# untitled.net
KiCad netlist of a schematic drawn in EAGLE
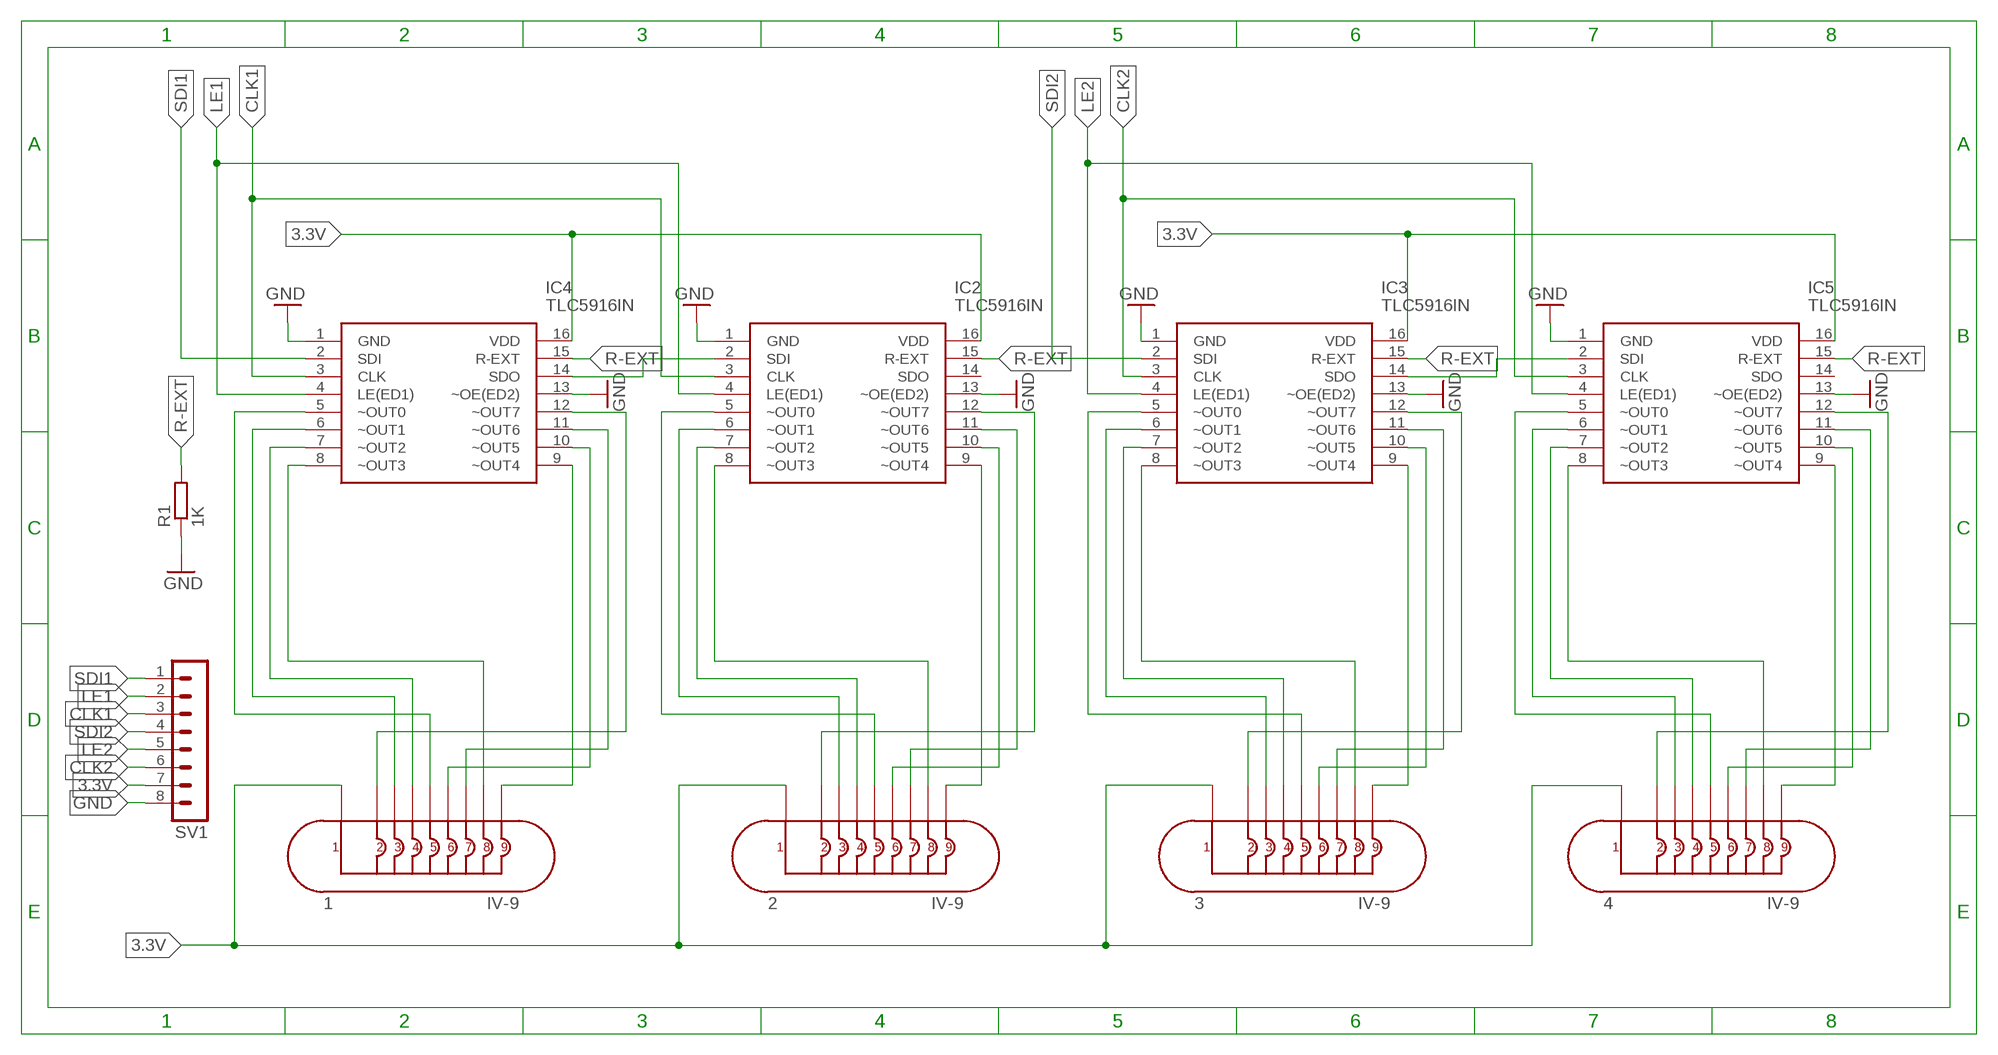
[diagram p0: schematic, sheet 1]
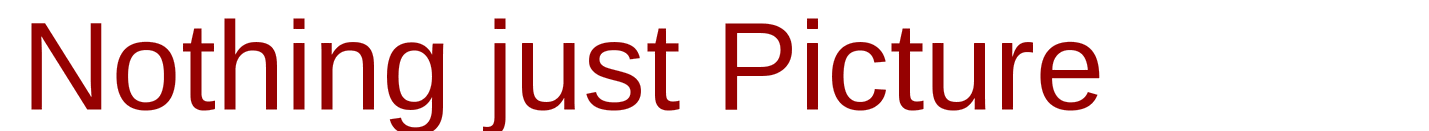
[diagram p1: schematic, sheet 2]

(export (version "E")
  (design (tool "Eeschema 10.0.6"))
  (components
    (comp (ref "1")
      (value "IV-9")
      (footprint "eagle-import:IV-9")
      (libsource (lib "eagle-import") (part "IV-9"))
    )
    (comp (ref "2")
      (value "IV-9")
      (footprint "eagle-import:IV-9")
      (libsource (lib "eagle-import") (part "IV-9"))
    )
    (comp (ref "3")
      (value "IV-9")
      (footprint "eagle-import:IV-9")
      (libsource (lib "eagle-import") (part "IV-9"))
    )
    (comp (ref "4")
      (value "IV-9")
      (footprint "eagle-import:IV-9")
      (libsource (lib "eagle-import") (part "IV-9"))
    )
    (comp (ref "IC2")
      (value "TLC5916IN")
      (footprint "eagle-import:DIP254P762X508-16")
      (fields (field (name "MOUSER_PART_NUMBER") "595-TLC5916IN"))
      (libsource (lib "eagle-import") (part "TLC5916IN"))
    )
    (comp (ref "IC3")
      (value "TLC5916IN")
      (footprint "eagle-import:DIP254P762X508-16")
      (fields (field (name "MOUSER_PART_NUMBER") "595-TLC5916IN"))
      (libsource (lib "eagle-import") (part "TLC5916IN"))
    )
    (comp (ref "IC4")
      (value "TLC5916IN")
      (footprint "eagle-import:DIP254P762X508-16")
      (fields (field (name "MOUSER_PART_NUMBER") "595-TLC5916IN"))
      (libsource (lib "eagle-import") (part "TLC5916IN"))
    )
    (comp (ref "IC5")
      (value "TLC5916IN")
      (footprint "eagle-import:DIP254P762X508-16")
      (fields (field (name "MOUSER_PART_NUMBER") "595-TLC5916IN"))
      (libsource (lib "eagle-import") (part "TLC5916IN"))
    )
    (comp (ref "R1")
      (value "1K")
      (footprint "eagle-import:R1206")
      (libsource (lib "eagle-import") (part "R-EU_R1206"))
    )
    (comp (ref "SV1")
      (value "MA08-1")
      (footprint "eagle-import:MA08-1")
      (libsource (lib "eagle-import") (part "MA08-1"))
    )
  )
  (nets
    (net (code "1") (name "3.3V") (class "Default")
      (node (ref "1") (pin "1") (pinfunction "1_1") (pintype "bidirectional"))
      (node (ref "2") (pin "1") (pinfunction "1_1") (pintype "bidirectional"))
      (node (ref "3") (pin "1") (pinfunction "1_1") (pintype "bidirectional"))
      (node (ref "4") (pin "1") (pinfunction "1_1") (pintype "bidirectional"))
      (node (ref "IC2") (pin "16") (pinfunction "VDD_16") (pintype "bidirectional"))
      (node (ref "IC3") (pin "16") (pinfunction "VDD_16") (pintype "bidirectional"))
      (node (ref "IC4") (pin "16") (pinfunction "VDD_16") (pintype "bidirectional"))
      (node (ref "IC5") (pin "16") (pinfunction "VDD_16") (pintype "bidirectional"))
      (node (ref "SV1") (pin "7") (pinfunction "7_7") (pintype "passive"))
    )
    (net (code "2") (name "CLK1") (class "Default")
      (node (ref "IC2") (pin "3") (pinfunction "CLK_3") (pintype "bidirectional"))
      (node (ref "IC4") (pin "3") (pinfunction "CLK_3") (pintype "bidirectional"))
      (node (ref "SV1") (pin "3") (pinfunction "3_3") (pintype "passive"))
    )
    (net (code "3") (name "CLK2") (class "Default")
      (node (ref "IC3") (pin "3") (pinfunction "CLK_3") (pintype "bidirectional"))
      (node (ref "IC5") (pin "3") (pinfunction "CLK_3") (pintype "bidirectional"))
      (node (ref "SV1") (pin "6") (pinfunction "6_6") (pintype "passive"))
    )
    (net (code "4") (name "GND") (class "Default")
      (node (ref "IC2") (pin "1") (pinfunction "GND_1") (pintype "bidirectional"))
      (node (ref "IC2") (pin "13") (pinfunction "~{OE(ED2})_13") (pintype "bidirectional"))
      (node (ref "IC3") (pin "1") (pinfunction "GND_1") (pintype "bidirectional"))
      (node (ref "IC3") (pin "13") (pinfunction "~{OE(ED2})_13") (pintype "bidirectional"))
      (node (ref "IC4") (pin "1") (pinfunction "GND_1") (pintype "bidirectional"))
      (node (ref "IC4") (pin "13") (pinfunction "~{OE(ED2})_13") (pintype "bidirectional"))
      (node (ref "IC5") (pin "1") (pinfunction "GND_1") (pintype "bidirectional"))
      (node (ref "IC5") (pin "13") (pinfunction "~{OE(ED2})_13") (pintype "bidirectional"))
      (node (ref "R1") (pin "1") (pinfunction "1_1") (pintype "passive"))
      (node (ref "SV1") (pin "8") (pinfunction "8_8") (pintype "passive"))
    )
    (net (code "5") (name "LE1") (class "Default")
      (node (ref "IC2") (pin "4") (pinfunction "LE(ED1)_4") (pintype "bidirectional"))
      (node (ref "IC4") (pin "4") (pinfunction "LE(ED1)_4") (pintype "bidirectional"))
      (node (ref "SV1") (pin "2") (pinfunction "2_2") (pintype "passive"))
    )
    (net (code "6") (name "LE2") (class "Default")
      (node (ref "IC3") (pin "4") (pinfunction "LE(ED1)_4") (pintype "bidirectional"))
      (node (ref "IC5") (pin "4") (pinfunction "LE(ED1)_4") (pintype "bidirectional"))
      (node (ref "SV1") (pin "5") (pinfunction "5_5") (pintype "passive"))
    )
    (net (code "7") (name "Net-(IC2-SDI)") (class "Default")
      (node (ref "IC2") (pin "2") (pinfunction "SDI_2") (pintype "bidirectional"))
      (node (ref "IC4") (pin "14") (pinfunction "SDO_14") (pintype "bidirectional"))
    )
    (net (code "8") (name "Net-(IC2-~{OUT0})") (class "Default")
      (node (ref "2") (pin "5") (pinfunction "5_5") (pintype "bidirectional"))
      (node (ref "IC2") (pin "5") (pinfunction "~{OUT0}_5") (pintype "bidirectional"))
    )
    (net (code "9") (name "Net-(IC2-~{OUT1})") (class "Default")
      (node (ref "2") (pin "3") (pinfunction "3_3") (pintype "bidirectional"))
      (node (ref "IC2") (pin "6") (pinfunction "~{OUT1}_6") (pintype "bidirectional"))
    )
    (net (code "10") (name "Net-(IC2-~{OUT2})") (class "Default")
      (node (ref "2") (pin "4") (pinfunction "4_4") (pintype "bidirectional"))
      (node (ref "IC2") (pin "7") (pinfunction "~{OUT2}_7") (pintype "bidirectional"))
    )
    (net (code "11") (name "Net-(IC2-~{OUT3})") (class "Default")
      (node (ref "2") (pin "8") (pinfunction "8_8") (pintype "bidirectional"))
      (node (ref "IC2") (pin "8") (pinfunction "~{OUT3}_8") (pintype "bidirectional"))
    )
    (net (code "12") (name "Net-(IC2-~{OUT4})") (class "Default")
      (node (ref "2") (pin "9") (pinfunction "9_9") (pintype "bidirectional"))
      (node (ref "IC2") (pin "9") (pinfunction "~{OUT4}_9") (pintype "bidirectional"))
    )
    (net (code "13") (name "Net-(IC2-~{OUT5})") (class "Default")
      (node (ref "2") (pin "6") (pinfunction "6_6") (pintype "bidirectional"))
      (node (ref "IC2") (pin "10") (pinfunction "~{OUT5}_10") (pintype "bidirectional"))
    )
    (net (code "14") (name "Net-(IC2-~{OUT6})") (class "Default")
      (node (ref "2") (pin "7") (pinfunction "7_7") (pintype "bidirectional"))
      (node (ref "IC2") (pin "11") (pinfunction "~{OUT6}_11") (pintype "bidirectional"))
    )
    (net (code "15") (name "Net-(IC2-~{OUT7})") (class "Default")
      (node (ref "2") (pin "2") (pinfunction "2_2") (pintype "bidirectional"))
      (node (ref "IC2") (pin "12") (pinfunction "~{OUT7}_12") (pintype "bidirectional"))
    )
    (net (code "16") (name "Net-(IC3-SDO)") (class "Default")
      (node (ref "IC3") (pin "14") (pinfunction "SDO_14") (pintype "bidirectional"))
      (node (ref "IC5") (pin "2") (pinfunction "SDI_2") (pintype "bidirectional"))
    )
    (net (code "17") (name "Net-(IC3-~{OUT0})") (class "Default")
      (node (ref "3") (pin "5") (pinfunction "5_5") (pintype "bidirectional"))
      (node (ref "IC3") (pin "5") (pinfunction "~{OUT0}_5") (pintype "bidirectional"))
    )
    (net (code "18") (name "Net-(IC3-~{OUT1})") (class "Default")
      (node (ref "3") (pin "3") (pinfunction "3_3") (pintype "bidirectional"))
      (node (ref "IC3") (pin "6") (pinfunction "~{OUT1}_6") (pintype "bidirectional"))
    )
    (net (code "19") (name "Net-(IC3-~{OUT2})") (class "Default")
      (node (ref "3") (pin "4") (pinfunction "4_4") (pintype "bidirectional"))
      (node (ref "IC3") (pin "7") (pinfunction "~{OUT2}_7") (pintype "bidirectional"))
    )
    (net (code "20") (name "Net-(IC3-~{OUT3})") (class "Default")
      (node (ref "3") (pin "8") (pinfunction "8_8") (pintype "bidirectional"))
      (node (ref "IC3") (pin "8") (pinfunction "~{OUT3}_8") (pintype "bidirectional"))
    )
    (net (code "21") (name "Net-(IC3-~{OUT4})") (class "Default")
      (node (ref "3") (pin "9") (pinfunction "9_9") (pintype "bidirectional"))
      (node (ref "IC3") (pin "9") (pinfunction "~{OUT4}_9") (pintype "bidirectional"))
    )
    (net (code "22") (name "Net-(IC3-~{OUT5})") (class "Default")
      (node (ref "3") (pin "6") (pinfunction "6_6") (pintype "bidirectional"))
      (node (ref "IC3") (pin "10") (pinfunction "~{OUT5}_10") (pintype "bidirectional"))
    )
    (net (code "23") (name "Net-(IC3-~{OUT6})") (class "Default")
      (node (ref "3") (pin "7") (pinfunction "7_7") (pintype "bidirectional"))
      (node (ref "IC3") (pin "11") (pinfunction "~{OUT6}_11") (pintype "bidirectional"))
    )
    (net (code "24") (name "Net-(IC3-~{OUT7})") (class "Default")
      (node (ref "3") (pin "2") (pinfunction "2_2") (pintype "bidirectional"))
      (node (ref "IC3") (pin "12") (pinfunction "~{OUT7}_12") (pintype "bidirectional"))
    )
    (net (code "25") (name "Net-(IC4-~{OUT0})") (class "Default")
      (node (ref "1") (pin "5") (pinfunction "5_5") (pintype "bidirectional"))
      (node (ref "IC4") (pin "5") (pinfunction "~{OUT0}_5") (pintype "bidirectional"))
    )
    (net (code "26") (name "Net-(IC4-~{OUT1})") (class "Default")
      (node (ref "1") (pin "3") (pinfunction "3_3") (pintype "bidirectional"))
      (node (ref "IC4") (pin "6") (pinfunction "~{OUT1}_6") (pintype "bidirectional"))
    )
    (net (code "27") (name "Net-(IC4-~{OUT2})") (class "Default")
      (node (ref "1") (pin "4") (pinfunction "4_4") (pintype "bidirectional"))
      (node (ref "IC4") (pin "7") (pinfunction "~{OUT2}_7") (pintype "bidirectional"))
    )
    (net (code "28") (name "Net-(IC4-~{OUT3})") (class "Default")
      (node (ref "1") (pin "8") (pinfunction "8_8") (pintype "bidirectional"))
      (node (ref "IC4") (pin "8") (pinfunction "~{OUT3}_8") (pintype "bidirectional"))
    )
    (net (code "29") (name "Net-(IC4-~{OUT4})") (class "Default")
      (node (ref "1") (pin "9") (pinfunction "9_9") (pintype "bidirectional"))
      (node (ref "IC4") (pin "9") (pinfunction "~{OUT4}_9") (pintype "bidirectional"))
    )
    (net (code "30") (name "Net-(IC4-~{OUT5})") (class "Default")
      (node (ref "1") (pin "6") (pinfunction "6_6") (pintype "bidirectional"))
      (node (ref "IC4") (pin "10") (pinfunction "~{OUT5}_10") (pintype "bidirectional"))
    )
    (net (code "31") (name "Net-(IC4-~{OUT6})") (class "Default")
      (node (ref "1") (pin "7") (pinfunction "7_7") (pintype "bidirectional"))
      (node (ref "IC4") (pin "11") (pinfunction "~{OUT6}_11") (pintype "bidirectional"))
    )
    (net (code "32") (name "Net-(IC4-~{OUT7})") (class "Default")
      (node (ref "1") (pin "2") (pinfunction "2_2") (pintype "bidirectional"))
      (node (ref "IC4") (pin "12") (pinfunction "~{OUT7}_12") (pintype "bidirectional"))
    )
    (net (code "33") (name "Net-(IC5-~{OUT0})") (class "Default")
      (node (ref "4") (pin "5") (pinfunction "5_5") (pintype "bidirectional"))
      (node (ref "IC5") (pin "5") (pinfunction "~{OUT0}_5") (pintype "bidirectional"))
    )
    (net (code "34") (name "Net-(IC5-~{OUT1})") (class "Default")
      (node (ref "4") (pin "3") (pinfunction "3_3") (pintype "bidirectional"))
      (node (ref "IC5") (pin "6") (pinfunction "~{OUT1}_6") (pintype "bidirectional"))
    )
    (net (code "35") (name "Net-(IC5-~{OUT2})") (class "Default")
      (node (ref "4") (pin "4") (pinfunction "4_4") (pintype "bidirectional"))
      (node (ref "IC5") (pin "7") (pinfunction "~{OUT2}_7") (pintype "bidirectional"))
    )
    (net (code "36") (name "Net-(IC5-~{OUT3})") (class "Default")
      (node (ref "4") (pin "8") (pinfunction "8_8") (pintype "bidirectional"))
      (node (ref "IC5") (pin "8") (pinfunction "~{OUT3}_8") (pintype "bidirectional"))
    )
    (net (code "37") (name "Net-(IC5-~{OUT4})") (class "Default")
      (node (ref "4") (pin "9") (pinfunction "9_9") (pintype "bidirectional"))
      (node (ref "IC5") (pin "9") (pinfunction "~{OUT4}_9") (pintype "bidirectional"))
    )
    (net (code "38") (name "Net-(IC5-~{OUT5})") (class "Default")
      (node (ref "4") (pin "6") (pinfunction "6_6") (pintype "bidirectional"))
      (node (ref "IC5") (pin "10") (pinfunction "~{OUT5}_10") (pintype "bidirectional"))
    )
    (net (code "39") (name "Net-(IC5-~{OUT6})") (class "Default")
      (node (ref "4") (pin "7") (pinfunction "7_7") (pintype "bidirectional"))
      (node (ref "IC5") (pin "11") (pinfunction "~{OUT6}_11") (pintype "bidirectional"))
    )
    (net (code "40") (name "Net-(IC5-~{OUT7})") (class "Default")
      (node (ref "4") (pin "2") (pinfunction "2_2") (pintype "bidirectional"))
      (node (ref "IC5") (pin "12") (pinfunction "~{OUT7}_12") (pintype "bidirectional"))
    )
    (net (code "41") (name "R-EXT") (class "Default")
      (node (ref "IC2") (pin "15") (pinfunction "R-EXT_15") (pintype "bidirectional"))
      (node (ref "IC3") (pin "15") (pinfunction "R-EXT_15") (pintype "bidirectional"))
      (node (ref "IC4") (pin "15") (pinfunction "R-EXT_15") (pintype "bidirectional"))
      (node (ref "IC5") (pin "15") (pinfunction "R-EXT_15") (pintype "bidirectional"))
      (node (ref "R1") (pin "2") (pinfunction "2_2") (pintype "passive"))
    )
    (net (code "42") (name "SDI1") (class "Default")
      (node (ref "IC4") (pin "2") (pinfunction "SDI_2") (pintype "bidirectional"))
      (node (ref "SV1") (pin "1") (pinfunction "1_1") (pintype "passive"))
    )
    (net (code "43") (name "SDI2") (class "Default")
      (node (ref "IC3") (pin "2") (pinfunction "SDI_2") (pintype "bidirectional"))
      (node (ref "SV1") (pin "4") (pinfunction "4_4") (pintype "passive"))
    )
    (net (code "44") (name "unconnected-(IC2-SDO-Pad14)") (class "Default")
      (node (ref "IC2") (pin "14") (pinfunction "SDO_14") (pintype "bidirectional"))
    )
    (net (code "45") (name "unconnected-(IC5-SDO-Pad14)") (class "Default")
      (node (ref "IC5") (pin "14") (pinfunction "SDO_14") (pintype "bidirectional"))
    )
  )
)
